# Puerto_VGA.net
KiCad netlist of a schematic drawn in Altium Designer
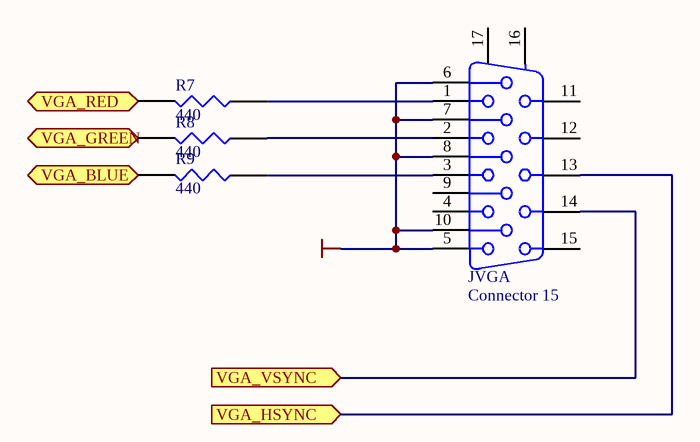
[diagram p0: Puerto VGA.SchDoc]

(export (version "E")
  (design (tool "Eeschema 10.0.6"))
  (components
    (comp (ref "JVGA")
      (value "Connector 15")
      (footprint "VGACON")
      (description "Receptacle Assembly, 15-Pin Connector")
      (fields
        (field (name "MANUFACTURER") "Generic Components")
        (field (name "PUBLISHER") "Altium Hobart Technology Centre")
      )
      (libsource (lib "Miscellaneous Connectors") (part "Connector 15"))
    )
    (comp (ref "R7") (value "440") (footprint "AXIAL-0.4") (libsource (lib "*") (part "RES1")))
    (comp (ref "R8") (value "440") (footprint "AXIAL-0.4") (libsource (lib "*") (part "RES1")))
    (comp (ref "R9") (value "440") (footprint "AXIAL-0.4") (libsource (lib "*") (part "RES1")))
  )
  (nets
    (net (code "1") (name "/VGA_BLUE") (class "Default")
      (node (ref "R9") (pin "2") (pinfunction "2_2") (pintype "passive"))
    )
    (net (code "2") (name "/VGA_GREEN") (class "Default")
      (node (ref "R8") (pin "2") (pinfunction "2_2") (pintype "passive"))
    )
    (net (code "3") (name "/VGA_HSYNC") (class "Default")
      (node (ref "JVGA") (pin "13") (pinfunction "13_13") (pintype "passive"))
    )
    (net (code "4") (name "/VGA_RED") (class "Default")
      (node (ref "R7") (pin "2") (pinfunction "2_2") (pintype "passive"))
    )
    (net (code "5") (name "/VGA_VSYNC") (class "Default")
      (node (ref "JVGA") (pin "14") (pinfunction "14_14") (pintype "passive"))
    )
    (net (code "6") (name "GND") (class "Default")
      (node (ref "JVGA") (pin "10") (pinfunction "10_10") (pintype "passive"))
      (node (ref "JVGA") (pin "5") (pinfunction "5_5") (pintype "passive"))
      (node (ref "JVGA") (pin "6") (pinfunction "6_6") (pintype "passive"))
      (node (ref "JVGA") (pin "7") (pinfunction "7_7") (pintype "passive"))
      (node (ref "JVGA") (pin "8") (pinfunction "8_8") (pintype "passive"))
    )
    (net (code "7") (name "Net-(JVGA-Pad1)") (class "Default")
      (node (ref "JVGA") (pin "1") (pinfunction "1_1") (pintype "passive"))
      (node (ref "R7") (pin "1") (pinfunction "1_1") (pintype "passive"))
    )
    (net (code "8") (name "Net-(JVGA-Pad2)") (class "Default")
      (node (ref "JVGA") (pin "2") (pinfunction "2_2") (pintype "passive"))
      (node (ref "R8") (pin "1") (pinfunction "1_1") (pintype "passive"))
    )
    (net (code "9") (name "Net-(JVGA-Pad3)") (class "Default")
      (node (ref "JVGA") (pin "3") (pinfunction "3_3") (pintype "passive"))
      (node (ref "R9") (pin "1") (pinfunction "1_1") (pintype "passive"))
    )
    (net (code "10") (name "unconnected-(JVGA-MH1-Pad16)") (class "Default")
      (node (ref "JVGA") (pin "16") (pinfunction "MH1_16") (pintype "passive"))
    )
    (net (code "11") (name "unconnected-(JVGA-MH2-Pad17)") (class "Default")
      (node (ref "JVGA") (pin "17") (pinfunction "MH2_17") (pintype "passive"))
    )
    (net (code "12") (name "unconnected-(JVGA-Pad4)") (class "Default")
      (node (ref "JVGA") (pin "4") (pinfunction "4_4") (pintype "passive"))
    )
    (net (code "13") (name "unconnected-(JVGA-Pad9)") (class "Default")
      (node (ref "JVGA") (pin "9") (pinfunction "9_9") (pintype "passive"))
    )
    (net (code "14") (name "unconnected-(JVGA-Pad11)") (class "Default")
      (node (ref "JVGA") (pin "11") (pinfunction "11_11") (pintype "passive"))
    )
    (net (code "15") (name "unconnected-(JVGA-Pad12)") (class "Default")
      (node (ref "JVGA") (pin "12") (pinfunction "12_12") (pintype "passive"))
    )
    (net (code "16") (name "unconnected-(JVGA-Pad15)") (class "Default")
      (node (ref "JVGA") (pin "15") (pinfunction "15_15") (pintype "passive"))
    )
  )
)
